# Energiezelle.net
KiCad netlist of a schematic drawn in EAGLE
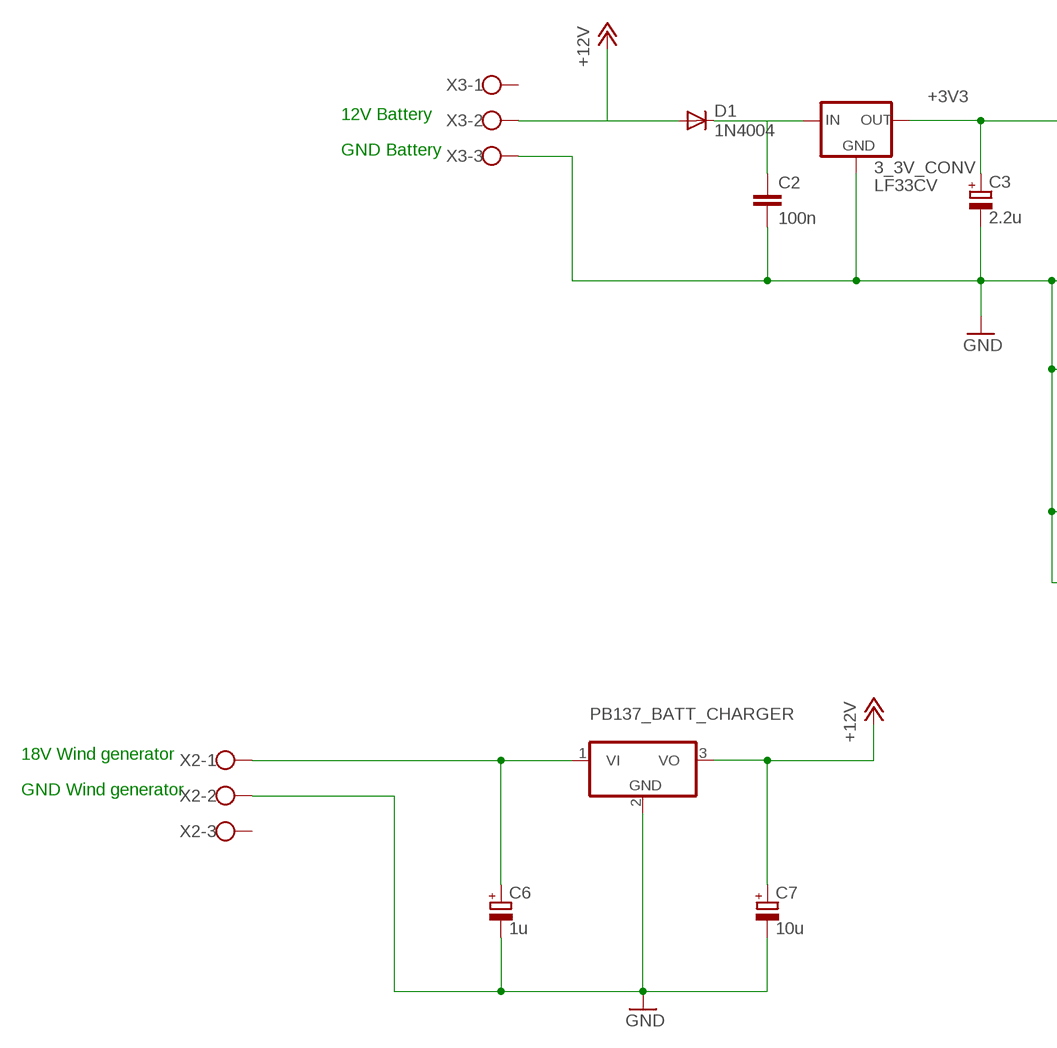
[diagram p0: schematic, sheet 1, part 1 of 2]
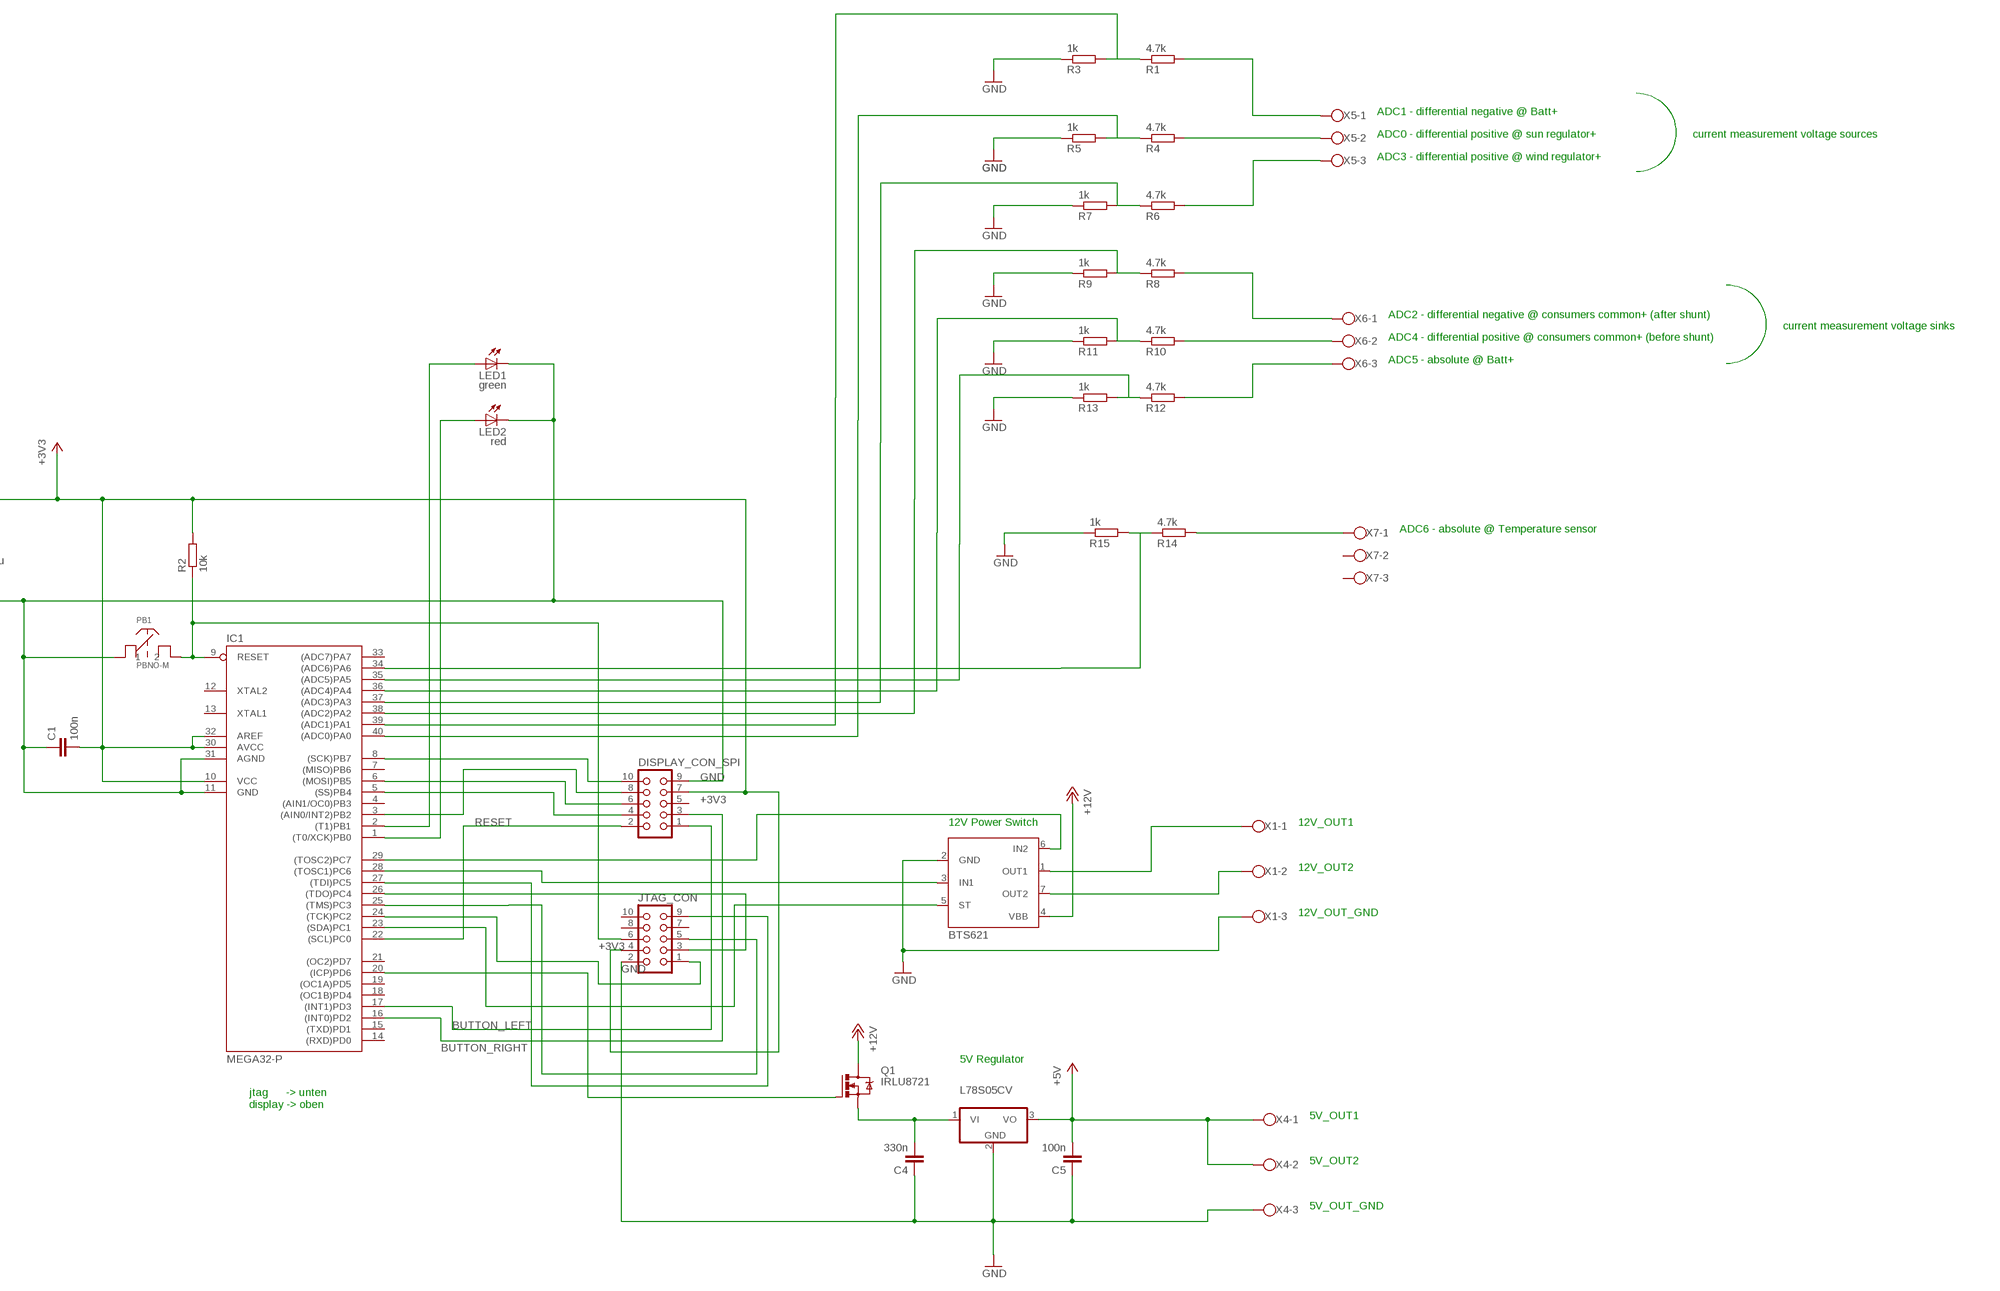
[diagram p1: schematic, sheet 1, part 2 of 2]

(export (version "E")
  (design (tool "Eeschema 10.0.6"))
  (components
    (comp (ref "3_3V_CONV")
      (value "LF33CV")
      (footprint "eagle-import:TO220S")
      (libsource (lib "eagle-import") (part "LFXXCVS"))
    )
    (comp (ref "C1")
      (value "100n")
      (footprint "eagle-import:C050-024X044")
      (libsource (lib "eagle-import") (part "C-EU050-024X044"))
    )
    (comp (ref "C2")
      (value "100n")
      (footprint "eagle-import:C050-024X044")
      (libsource (lib "eagle-import") (part "C-EU050-024X044"))
    )
    (comp (ref "C3")
      (value "2.2u")
      (footprint "eagle-import:E2,5-6E")
      (libsource (lib "eagle-import") (part "CPOL-EUE2,5-6E"))
    )
    (comp (ref "C4")
      (value "330n")
      (footprint "eagle-import:C050-024X044")
      (libsource (lib "eagle-import") (part "C-EU050-024X044"))
    )
    (comp (ref "C5")
      (value "100n")
      (footprint "eagle-import:C050-024X044")
      (libsource (lib "eagle-import") (part "C-EU050-024X044"))
    )
    (comp (ref "C6")
      (value "1u")
      (footprint "eagle-import:E2,5-6E")
      (libsource (lib "eagle-import") (part "CPOL-EUE2,5-6E"))
    )
    (comp (ref "C7")
      (value "10u")
      (footprint "eagle-import:E2,5-6E")
      (libsource (lib "eagle-import") (part "CPOL-EUE2,5-6E"))
    )
    (comp (ref "D1")
      (value "1N4004")
      (footprint "eagle-import:DO41-10")
      (libsource (lib "eagle-import") (part "1N4004"))
    )
    (comp (ref "DISPLAY_CON_SPI")
      (value "CON10L")
      (footprint "eagle-import:CON10L")
      (libsource (lib "eagle-import") (part "CON10L"))
    )
    (comp (ref "IC1")
      (value "MEGA32-P")
      (footprint "eagle-import:DIL40")
      (libsource (lib "eagle-import") (part "MEGA32-P"))
    )
    (comp (ref "IC2")
      (value "BTS621")
      (footprint "eagle-import:P-TO220-7-11")
      (libsource (lib "eagle-import") (part "TLE5205-2"))
    )
    (comp (ref "JTAG_CON")
      (value "CON10L")
      (footprint "eagle-import:CON10L")
      (libsource (lib "eagle-import") (part "CON10L"))
    )
    (comp (ref "L78S05CV")
      (value "788TV")
      (footprint "eagle-import:TO220V")
      (libsource (lib "eagle-import") (part "78TV8"))
    )
    (comp (ref "LED1")
      (value "green")
      (footprint "eagle-import:LSU260")
      (libsource (lib "eagle-import") (part "LEDLSU260"))
    )
    (comp (ref "LED2")
      (value "red")
      (footprint "eagle-import:LSU260")
      (libsource (lib "eagle-import") (part "LEDLSU260"))
    )
    (comp (ref "PB1")
      (value "PBNO-M")
      (footprint "eagle-import:PBNO-M")
      (libsource (lib "eagle-import") (part "PBNO-M"))
    )
    (comp (ref "PB137_BATT_CHARGER")
      (value "788TV")
      (footprint "eagle-import:TO220V")
      (libsource (lib "eagle-import") (part "78TV8"))
    )
    (comp (ref "Q1")
      (value "IRLU8721")
      (footprint "eagle-import:TO220BV")
      (libsource (lib "eagle-import") (part "IRF540"))
    )
    (comp (ref "R1")
      (value "4.7k")
      (footprint "eagle-import:0207_10")
      (libsource (lib "eagle-import") (part "R-EU_0207/10"))
    )
    (comp (ref "R2")
      (value "10k")
      (footprint "eagle-import:0207_10")
      (libsource (lib "eagle-import") (part "R-EU_0207/10"))
    )
    (comp (ref "R3")
      (value "1k")
      (footprint "eagle-import:0207_10")
      (libsource (lib "eagle-import") (part "R-EU_0207/10"))
    )
    (comp (ref "R4")
      (value "4.7k")
      (footprint "eagle-import:0207_10")
      (libsource (lib "eagle-import") (part "R-EU_0207/10"))
    )
    (comp (ref "R5")
      (value "1k")
      (footprint "eagle-import:0207_10")
      (libsource (lib "eagle-import") (part "R-EU_0207/10"))
    )
    (comp (ref "R6")
      (value "4.7k")
      (footprint "eagle-import:0207_10")
      (libsource (lib "eagle-import") (part "R-EU_0207/10"))
    )
    (comp (ref "R7")
      (value "1k")
      (footprint "eagle-import:0207_10")
      (libsource (lib "eagle-import") (part "R-EU_0207/10"))
    )
    (comp (ref "R8")
      (value "4.7k")
      (footprint "eagle-import:0207_10")
      (libsource (lib "eagle-import") (part "R-EU_0207/10"))
    )
    (comp (ref "R9")
      (value "1k")
      (footprint "eagle-import:0207_10")
      (libsource (lib "eagle-import") (part "R-EU_0207/10"))
    )
    (comp (ref "R10")
      (value "4.7k")
      (footprint "eagle-import:0207_10")
      (libsource (lib "eagle-import") (part "R-EU_0207/10"))
    )
    (comp (ref "R11")
      (value "1k")
      (footprint "eagle-import:0207_10")
      (libsource (lib "eagle-import") (part "R-EU_0207/10"))
    )
    (comp (ref "R12")
      (value "4.7k")
      (footprint "eagle-import:0207_10")
      (libsource (lib "eagle-import") (part "R-EU_0207/10"))
    )
    (comp (ref "R13")
      (value "1k")
      (footprint "eagle-import:0207_10")
      (libsource (lib "eagle-import") (part "R-EU_0207/10"))
    )
    (comp (ref "R14")
      (value "4.7k")
      (footprint "eagle-import:0207_10")
      (libsource (lib "eagle-import") (part "R-EU_0207/10"))
    )
    (comp (ref "R15")
      (value "1k")
      (footprint "eagle-import:0207_10")
      (libsource (lib "eagle-import") (part "R-EU_0207/10"))
    )
    (comp (ref "X1")
      (value "W237-103")
      (footprint "eagle-import:W237-103")
      (fields (field (name "MPN") "237-103"))
      (libsource (lib "eagle-import") (part "W237-103"))
    )
    (comp (ref "X2")
      (value "W237-103")
      (footprint "eagle-import:W237-103")
      (fields (field (name "MPN") "237-103"))
      (libsource (lib "eagle-import") (part "W237-103"))
    )
    (comp (ref "X3")
      (value "W237-103")
      (footprint "eagle-import:W237-103")
      (fields (field (name "MPN") "237-103"))
      (libsource (lib "eagle-import") (part "W237-103"))
    )
    (comp (ref "X4")
      (value "W237-103")
      (footprint "eagle-import:W237-103")
      (fields (field (name "MPN") "237-103"))
      (libsource (lib "eagle-import") (part "W237-103"))
    )
    (comp (ref "X5")
      (value "W237-103")
      (footprint "eagle-import:W237-103")
      (fields (field (name "MPN") "237-103"))
      (libsource (lib "eagle-import") (part "W237-103"))
    )
    (comp (ref "X6")
      (value "W237-103")
      (footprint "eagle-import:W237-103")
      (fields (field (name "MPN") "237-103"))
      (libsource (lib "eagle-import") (part "W237-103"))
    )
    (comp (ref "X7")
      (value "W237-103")
      (footprint "eagle-import:W237-103")
      (fields (field (name "MPN") "237-103"))
      (libsource (lib "eagle-import") (part "W237-103"))
    )
  )
  (nets
    (net (code "1") (name "+3V3") (class "Default")
      (node (ref "3_3V_CONV") (pin "3") (pinfunction "OUT_3") (pintype "passive"))
      (node (ref "C1") (pin "2") (pinfunction "2_2") (pintype "passive"))
      (node (ref "C3") (pin "+") (pinfunction "+_+") (pintype "passive"))
      (node (ref "DISPLAY_CON_SPI") (pin "7") (pinfunction "7_7") (pintype "passive"))
      (node (ref "IC1") (pin "10") (pinfunction "VCC_10") (pintype "power_in"))
      (node (ref "IC1") (pin "30") (pinfunction "AVCC_30") (pintype "power_in"))
      (node (ref "IC1") (pin "32") (pinfunction "AREF_32") (pintype "power_in"))
      (node (ref "JTAG_CON") (pin "4") (pinfunction "4_4") (pintype "passive"))
      (node (ref "R2") (pin "2") (pinfunction "2_2") (pintype "passive"))
    )
    (net (code "2") (name "+5V") (class "Default")
      (node (ref "C5") (pin "2") (pinfunction "2_2") (pintype "passive"))
      (node (ref "L78S05CV") (pin "3") (pinfunction "VO_3") (pintype "passive"))
      (node (ref "X4") (pin "1") (pinfunction "KL_1") (pintype "passive"))
      (node (ref "X4") (pin "2") (pinfunction "KL_2") (pintype "passive"))
    )
    (net (code "3") (name "+12V") (class "Default")
      (node (ref "C7") (pin "+") (pinfunction "+_+") (pintype "passive"))
      (node (ref "D1") (pin "A") (pinfunction "A_A") (pintype "passive"))
      (node (ref "IC2") (pin "4") (pinfunction "VBB_4") (pintype "input"))
      (node (ref "PB137_BATT_CHARGER") (pin "3") (pinfunction "VO_3") (pintype "passive"))
      (node (ref "Q1") (pin "D") (pinfunction "D_D") (pintype "passive"))
      (node (ref "X3") (pin "2") (pinfunction "KL_2") (pintype "passive"))
    )
    (net (code "4") (name "/BUTTON_LEFT") (class "Default")
      (node (ref "DISPLAY_CON_SPI") (pin "1") (pinfunction "1_1") (pintype "passive"))
      (node (ref "IC1") (pin "17") (pinfunction "(INT1)PD3_17") (pintype "bidirectional"))
    )
    (net (code "5") (name "/BUTTON_RIGHT") (class "Default")
      (node (ref "DISPLAY_CON_SPI") (pin "3") (pinfunction "3_3") (pintype "passive"))
      (node (ref "IC1") (pin "16") (pinfunction "(INT0)PD2_16") (pintype "bidirectional"))
    )
    (net (code "6") (name "/RESET") (class "Default")
      (node (ref "DISPLAY_CON_SPI") (pin "2") (pinfunction "2_2") (pintype "passive"))
      (node (ref "IC1") (pin "22") (pinfunction "(SCL)PC0_22") (pintype "bidirectional"))
    )
    (net (code "7") (name "GND") (class "Default")
      (node (ref "3_3V_CONV") (pin "2") (pinfunction "GND_2") (pintype "input"))
      (node (ref "C1") (pin "1") (pinfunction "1_1") (pintype "passive"))
      (node (ref "C2") (pin "2") (pinfunction "2_2") (pintype "passive"))
      (node (ref "C3") (pin "-") (pinfunction "-_-") (pintype "passive"))
      (node (ref "C4") (pin "1") (pinfunction "1_1") (pintype "passive"))
      (node (ref "C5") (pin "1") (pinfunction "1_1") (pintype "passive"))
      (node (ref "C6") (pin "-") (pinfunction "-_-") (pintype "passive"))
      (node (ref "C7") (pin "-") (pinfunction "-_-") (pintype "passive"))
      (node (ref "DISPLAY_CON_SPI") (pin "9") (pinfunction "9_9") (pintype "passive"))
      (node (ref "IC1") (pin "11") (pinfunction "GND_11") (pintype "power_in"))
      (node (ref "IC1") (pin "31") (pinfunction "AGND_31") (pintype "power_in"))
      (node (ref "IC2") (pin "2") (pinfunction "GND_2") (pintype "power_in"))
      (node (ref "JTAG_CON") (pin "2") (pinfunction "2_2") (pintype "passive"))
      (node (ref "L78S05CV") (pin "2") (pinfunction "GND_2") (pintype "passive"))
      (node (ref "LED1") (pin "K") (pinfunction "C_K") (pintype "passive"))
      (node (ref "LED2") (pin "K") (pinfunction "C_K") (pintype "passive"))
      (node (ref "PB1") (pin "P$1") (pinfunction "1_P$1") (pintype "passive"))
      (node (ref "PB137_BATT_CHARGER") (pin "2") (pinfunction "GND_2") (pintype "passive"))
      (node (ref "R11") (pin "1") (pinfunction "1_1") (pintype "passive"))
      (node (ref "R13") (pin "1") (pinfunction "1_1") (pintype "passive"))
      (node (ref "R15") (pin "1") (pinfunction "1_1") (pintype "passive"))
      (node (ref "R3") (pin "1") (pinfunction "1_1") (pintype "passive"))
      (node (ref "R5") (pin "1") (pinfunction "1_1") (pintype "passive"))
      (node (ref "R7") (pin "1") (pinfunction "1_1") (pintype "passive"))
      (node (ref "R9") (pin "1") (pinfunction "1_1") (pintype "passive"))
      (node (ref "X1") (pin "3") (pinfunction "KL_3") (pintype "passive"))
      (node (ref "X2") (pin "2") (pinfunction "KL_2") (pintype "passive"))
      (node (ref "X3") (pin "3") (pinfunction "KL_3") (pintype "passive"))
      (node (ref "X4") (pin "3") (pinfunction "KL_3") (pintype "passive"))
    )
    (net (code "8") (name "Net-(3_3V_CONV-IN)") (class "Default")
      (node (ref "3_3V_CONV") (pin "1") (pinfunction "IN_1") (pintype "input"))
      (node (ref "C2") (pin "1") (pinfunction "1_1") (pintype "passive"))
      (node (ref "D1") (pin "C") (pinfunction "C_C") (pintype "passive"))
    )
    (net (code "9") (name "Net-(IC1-(ADC0)PA0)") (class "Default")
      (node (ref "IC1") (pin "40") (pinfunction "(ADC0)PA0_40") (pintype "bidirectional"))
      (node (ref "R4") (pin "1") (pinfunction "1_1") (pintype "passive"))
      (node (ref "R5") (pin "2") (pinfunction "2_2") (pintype "passive"))
    )
    (net (code "10") (name "Net-(IC1-(ADC1)PA1)") (class "Default")
      (node (ref "IC1") (pin "39") (pinfunction "(ADC1)PA1_39") (pintype "bidirectional"))
      (node (ref "R1") (pin "1") (pinfunction "1_1") (pintype "passive"))
      (node (ref "R3") (pin "2") (pinfunction "2_2") (pintype "passive"))
    )
    (net (code "11") (name "Net-(IC1-(ADC2)PA2)") (class "Default")
      (node (ref "IC1") (pin "38") (pinfunction "(ADC2)PA2_38") (pintype "bidirectional"))
      (node (ref "R8") (pin "1") (pinfunction "1_1") (pintype "passive"))
      (node (ref "R9") (pin "2") (pinfunction "2_2") (pintype "passive"))
    )
    (net (code "12") (name "Net-(IC1-(ADC3)PA3)") (class "Default")
      (node (ref "IC1") (pin "37") (pinfunction "(ADC3)PA3_37") (pintype "bidirectional"))
      (node (ref "R6") (pin "1") (pinfunction "1_1") (pintype "passive"))
      (node (ref "R7") (pin "2") (pinfunction "2_2") (pintype "passive"))
    )
    (net (code "13") (name "Net-(IC1-(ADC4)PA4)") (class "Default")
      (node (ref "IC1") (pin "36") (pinfunction "(ADC4)PA4_36") (pintype "bidirectional"))
      (node (ref "R10") (pin "1") (pinfunction "1_1") (pintype "passive"))
      (node (ref "R11") (pin "2") (pinfunction "2_2") (pintype "passive"))
    )
    (net (code "14") (name "Net-(IC1-(ADC5)PA5)") (class "Default")
      (node (ref "IC1") (pin "35") (pinfunction "(ADC5)PA5_35") (pintype "bidirectional"))
      (node (ref "R12") (pin "1") (pinfunction "1_1") (pintype "passive"))
      (node (ref "R13") (pin "2") (pinfunction "2_2") (pintype "passive"))
    )
    (net (code "15") (name "Net-(IC1-(ADC6)PA6)") (class "Default")
      (node (ref "IC1") (pin "34") (pinfunction "(ADC6)PA6_34") (pintype "bidirectional"))
      (node (ref "R14") (pin "1") (pinfunction "1_1") (pintype "passive"))
      (node (ref "R15") (pin "2") (pinfunction "2_2") (pintype "passive"))
    )
    (net (code "16") (name "Net-(IC1-(AIN0{slash}INT2)PB2)") (class "Default")
      (node (ref "DISPLAY_CON_SPI") (pin "8") (pinfunction "8_8") (pintype "passive"))
      (node (ref "IC1") (pin "3") (pinfunction "(AIN0/INT2)PB2_3") (pintype "bidirectional"))
    )
    (net (code "17") (name "Net-(IC1-(ICP)PD6)") (class "Default")
      (node (ref "IC1") (pin "20") (pinfunction "(ICP)PD6_20") (pintype "bidirectional"))
      (node (ref "Q1") (pin "G") (pinfunction "G_G") (pintype "passive"))
    )
    (net (code "18") (name "Net-(IC1-(MOSI)PB5)") (class "Default")
      (node (ref "DISPLAY_CON_SPI") (pin "6") (pinfunction "6_6") (pintype "passive"))
      (node (ref "IC1") (pin "6") (pinfunction "(MOSI)PB5_6") (pintype "bidirectional"))
    )
    (net (code "19") (name "Net-(IC1-(SCK)PB7)") (class "Default")
      (node (ref "DISPLAY_CON_SPI") (pin "10") (pinfunction "10_10") (pintype "passive"))
      (node (ref "IC1") (pin "8") (pinfunction "(SCK)PB7_8") (pintype "bidirectional"))
    )
    (net (code "20") (name "Net-(IC1-(SDA)PC1)") (class "Default")
      (node (ref "IC1") (pin "23") (pinfunction "(SDA)PC1_23") (pintype "bidirectional"))
      (node (ref "IC2") (pin "5") (pinfunction "ST_5") (pintype "input"))
    )
    (net (code "21") (name "Net-(IC1-(SS)PB4)") (class "Default")
      (node (ref "DISPLAY_CON_SPI") (pin "4") (pinfunction "4_4") (pintype "passive"))
      (node (ref "IC1") (pin "5") (pinfunction "(SS)PB4_5") (pintype "bidirectional"))
    )
    (net (code "22") (name "Net-(IC1-(T0{slash}XCK)PB0)") (class "Default")
      (node (ref "IC1") (pin "1") (pinfunction "(T0/XCK)PB0_1") (pintype "bidirectional"))
      (node (ref "LED2") (pin "A") (pinfunction "A_A") (pintype "passive"))
    )
    (net (code "23") (name "Net-(IC1-(T1)PB1)") (class "Default")
      (node (ref "IC1") (pin "2") (pinfunction "(T1)PB1_2") (pintype "bidirectional"))
      (node (ref "LED1") (pin "A") (pinfunction "A_A") (pintype "passive"))
    )
    (net (code "24") (name "Net-(IC1-(TCK)PC2)") (class "Default")
      (node (ref "IC1") (pin "24") (pinfunction "(TCK)PC2_24") (pintype "bidirectional"))
      (node (ref "JTAG_CON") (pin "1") (pinfunction "1_1") (pintype "passive"))
    )
    (net (code "25") (name "Net-(IC1-(TDI)PC5)") (class "Default")
      (node (ref "IC1") (pin "27") (pinfunction "(TDI)PC5_27") (pintype "bidirectional"))
      (node (ref "JTAG_CON") (pin "9") (pinfunction "9_9") (pintype "passive"))
    )
    (net (code "26") (name "Net-(IC1-(TDO)PC4)") (class "Default")
      (node (ref "IC1") (pin "26") (pinfunction "(TDO)PC4_26") (pintype "bidirectional"))
      (node (ref "JTAG_CON") (pin "3") (pinfunction "3_3") (pintype "passive"))
    )
    (net (code "27") (name "Net-(IC1-(TMS)PC3)") (class "Default")
      (node (ref "IC1") (pin "25") (pinfunction "(TMS)PC3_25") (pintype "bidirectional"))
      (node (ref "JTAG_CON") (pin "5") (pinfunction "5_5") (pintype "passive"))
    )
    (net (code "28") (name "Net-(IC1-(TOSC1)PC6)") (class "Default")
      (node (ref "IC1") (pin "28") (pinfunction "(TOSC1)PC6_28") (pintype "bidirectional"))
      (node (ref "IC2") (pin "3") (pinfunction "IN1_3") (pintype "input"))
    )
    (net (code "29") (name "Net-(IC1-(TOSC2)PC7)") (class "Default")
      (node (ref "IC1") (pin "29") (pinfunction "(TOSC2)PC7_29") (pintype "bidirectional"))
      (node (ref "IC2") (pin "6") (pinfunction "IN2_6") (pintype "input"))
    )
    (net (code "30") (name "Net-(IC1-RESET)") (class "Default")
      (node (ref "IC1") (pin "9") (pinfunction "RESET_9") (pintype "input"))
      (node (ref "JTAG_CON") (pin "6") (pinfunction "6_6") (pintype "passive"))
      (node (ref "PB1") (pin "P$2") (pinfunction "2_P$2") (pintype "passive"))
      (node (ref "R2") (pin "1") (pinfunction "1_1") (pintype "passive"))
    )
    (net (code "31") (name "Net-(IC2-OUT1)") (class "Default")
      (node (ref "IC2") (pin "1") (pinfunction "OUT1_1") (pintype "output"))
      (node (ref "X1") (pin "1") (pinfunction "KL_1") (pintype "passive"))
    )
    (net (code "32") (name "Net-(IC2-OUT2)") (class "Default")
      (node (ref "IC2") (pin "7") (pinfunction "OUT2_7") (pintype "output"))
      (node (ref "X1") (pin "2") (pinfunction "KL_2") (pintype "passive"))
    )
    (net (code "33") (name "Net-(L78S05CV-VI)") (class "Default")
      (node (ref "C4") (pin "2") (pinfunction "2_2") (pintype "passive"))
      (node (ref "L78S05CV") (pin "1") (pinfunction "VI_1") (pintype "input"))
      (node (ref "Q1") (pin "S") (pinfunction "S_S") (pintype "passive"))
    )
    (net (code "34") (name "Net-(PB137_BATT_CHARGER-VI)") (class "Default")
      (node (ref "C6") (pin "+") (pinfunction "+_+") (pintype "passive"))
      (node (ref "PB137_BATT_CHARGER") (pin "1") (pinfunction "VI_1") (pintype "input"))
      (node (ref "X2") (pin "1") (pinfunction "KL_1") (pintype "passive"))
    )
    (net (code "35") (name "Net-(X5A-KL)") (class "Default")
      (node (ref "R1") (pin "2") (pinfunction "2_2") (pintype "passive"))
      (node (ref "X5") (pin "1") (pinfunction "KL_1") (pintype "passive"))
    )
    (net (code "36") (name "Net-(X5B-KL)") (class "Default")
      (node (ref "R4") (pin "2") (pinfunction "2_2") (pintype "passive"))
      (node (ref "X5") (pin "2") (pinfunction "KL_2") (pintype "passive"))
    )
    (net (code "37") (name "Net-(X5C-KL)") (class "Default")
      (node (ref "R6") (pin "2") (pinfunction "2_2") (pintype "passive"))
      (node (ref "X5") (pin "3") (pinfunction "KL_3") (pintype "passive"))
    )
    (net (code "38") (name "Net-(X6A-KL)") (class "Default")
      (node (ref "R8") (pin "2") (pinfunction "2_2") (pintype "passive"))
      (node (ref "X6") (pin "1") (pinfunction "KL_1") (pintype "passive"))
    )
    (net (code "39") (name "Net-(X6B-KL)") (class "Default")
      (node (ref "R10") (pin "2") (pinfunction "2_2") (pintype "passive"))
      (node (ref "X6") (pin "2") (pinfunction "KL_2") (pintype "passive"))
    )
    (net (code "40") (name "Net-(X6C-KL)") (class "Default")
      (node (ref "R12") (pin "2") (pinfunction "2_2") (pintype "passive"))
      (node (ref "X6") (pin "3") (pinfunction "KL_3") (pintype "passive"))
    )
    (net (code "41") (name "Net-(X7A-KL)") (class "Default")
      (node (ref "R14") (pin "2") (pinfunction "2_2") (pintype "passive"))
      (node (ref "X7") (pin "1") (pinfunction "KL_1") (pintype "passive"))
    )
    (net (code "42") (name "unconnected-(DISPLAY_CON_SPI-Pad5)") (class "Default")
      (node (ref "DISPLAY_CON_SPI") (pin "5") (pinfunction "5_5") (pintype "passive"))
    )
    (net (code "43") (name "unconnected-(IC1-(ADC7)PA7-Pad33)") (class "Default")
      (node (ref "IC1") (pin "33") (pinfunction "(ADC7)PA7_33") (pintype "bidirectional"))
    )
    (net (code "44") (name "unconnected-(IC1-(AIN1{slash}OC0)PB3-Pad4)") (class "Default")
      (node (ref "IC1") (pin "4") (pinfunction "(AIN1/OC0)PB3_4") (pintype "bidirectional"))
    )
    (net (code "45") (name "unconnected-(IC1-(MISO)PB6-Pad7)") (class "Default")
      (node (ref "IC1") (pin "7") (pinfunction "(MISO)PB6_7") (pintype "bidirectional"))
    )
    (net (code "46") (name "unconnected-(IC1-(OC1A)PD5-Pad19)") (class "Default")
      (node (ref "IC1") (pin "19") (pinfunction "(OC1A)PD5_19") (pintype "bidirectional"))
    )
    (net (code "47") (name "unconnected-(IC1-(OC1B)PD4-Pad18)") (class "Default")
      (node (ref "IC1") (pin "18") (pinfunction "(OC1B)PD4_18") (pintype "bidirectional"))
    )
    (net (code "48") (name "unconnected-(IC1-(OC2)PD7-Pad21)") (class "Default")
      (node (ref "IC1") (pin "21") (pinfunction "(OC2)PD7_21") (pintype "bidirectional"))
    )
    (net (code "49") (name "unconnected-(IC1-(RXD)PD0-Pad14)") (class "Default")
      (node (ref "IC1") (pin "14") (pinfunction "(RXD)PD0_14") (pintype "bidirectional"))
    )
    (net (code "50") (name "unconnected-(IC1-(TXD)PD1-Pad15)") (class "Default")
      (node (ref "IC1") (pin "15") (pinfunction "(TXD)PD1_15") (pintype "bidirectional"))
    )
    (net (code "51") (name "unconnected-(IC1-XTAL1-Pad13)") (class "Default")
      (node (ref "IC1") (pin "13") (pinfunction "XTAL1_13") (pintype "bidirectional"))
    )
    (net (code "52") (name "unconnected-(IC1-XTAL2-Pad12)") (class "Default")
      (node (ref "IC1") (pin "12") (pinfunction "XTAL2_12") (pintype "bidirectional"))
    )
    (net (code "53") (name "unconnected-(JTAG_CON-Pad7)") (class "Default")
      (node (ref "JTAG_CON") (pin "7") (pinfunction "7_7") (pintype "passive"))
    )
    (net (code "54") (name "unconnected-(JTAG_CON-Pad8)") (class "Default")
      (node (ref "JTAG_CON") (pin "8") (pinfunction "8_8") (pintype "passive"))
    )
    (net (code "55") (name "unconnected-(JTAG_CON-Pad10)") (class "Default")
      (node (ref "JTAG_CON") (pin "10") (pinfunction "10_10") (pintype "passive"))
    )
    (net (code "56") (name "unconnected-(X2C-KL-Pad3)") (class "Default")
      (node (ref "X2") (pin "3") (pinfunction "KL_3") (pintype "passive"))
    )
    (net (code "57") (name "unconnected-(X3A-KL-Pad1)") (class "Default")
      (node (ref "X3") (pin "1") (pinfunction "KL_1") (pintype "passive"))
    )
    (net (code "58") (name "unconnected-(X7B-KL-Pad2)") (class "Default")
      (node (ref "X7") (pin "2") (pinfunction "KL_2") (pintype "passive"))
    )
    (net (code "59") (name "unconnected-(X7C-KL-Pad3)") (class "Default")
      (node (ref "X7") (pin "3") (pinfunction "KL_3") (pintype "passive"))
    )
  )
)
